# Micro.net
KiCad netlist of a schematic drawn in Altium Designer
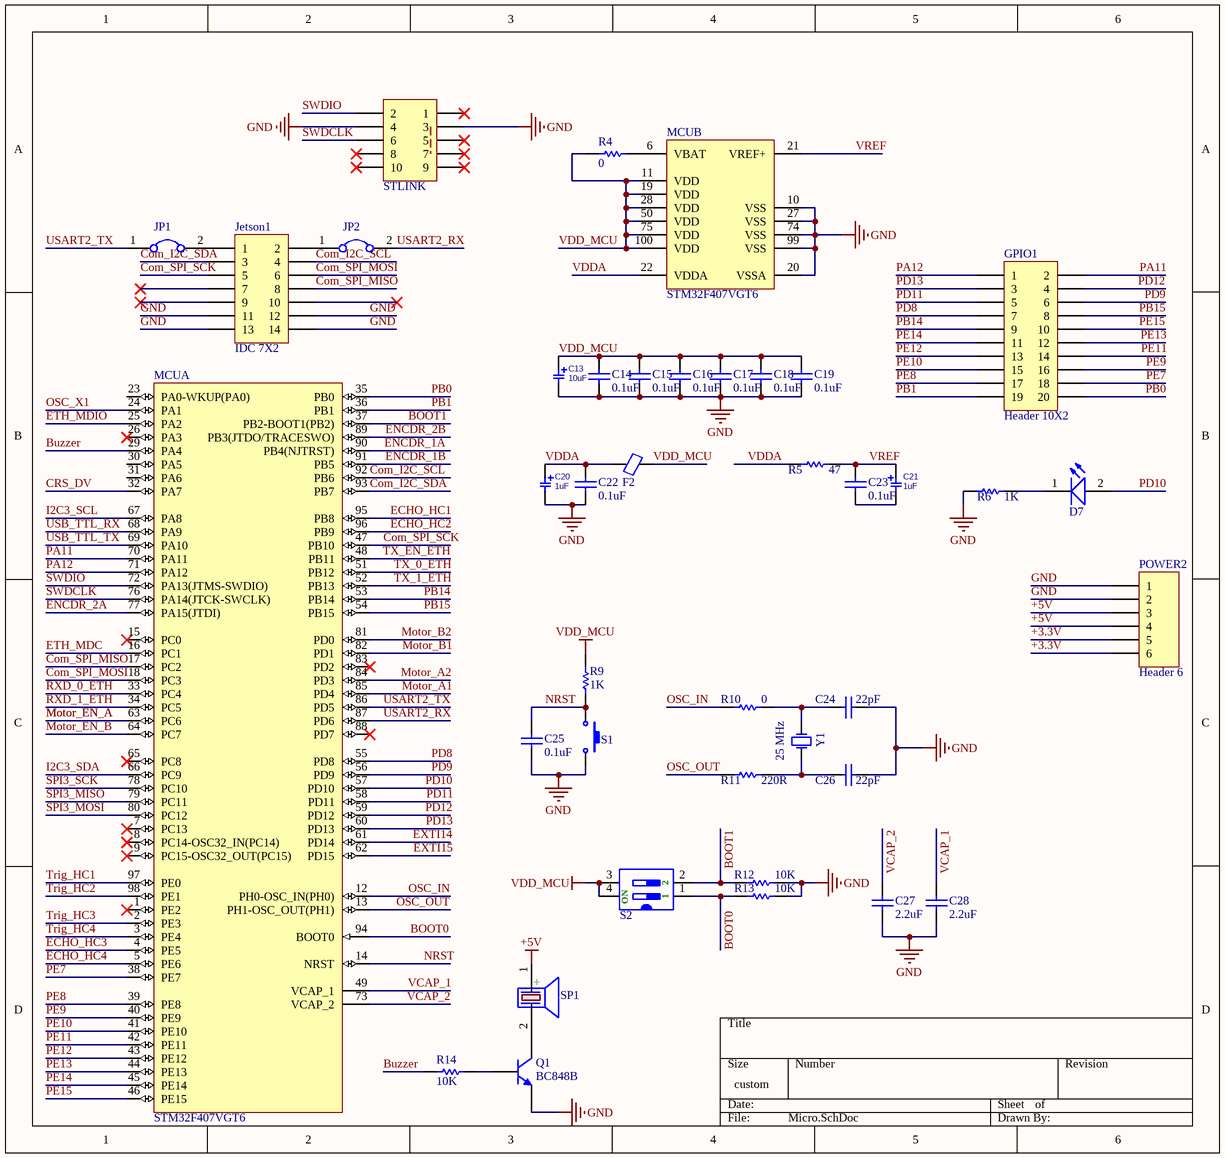
[diagram p0: Micro.SchDoc]

(export (version "E")
  (design (tool "Eeschema 10.0.6"))
  (components
    (comp (ref "C13")
      (value "10uF")
      (footprint "C_TN_6032")
      (description "CAP, SMD, TAN,")
      (libsource (lib "Passive") (part "CAP_SMD_TAN"))
    )
    (comp (ref "C14")
      (value "0.1uF")
      (footprint "CAPC3413X12N")
      (description "CAP 0805")
      (fields (field (name "DESIGNER") "Abbas Basereh"))
      (libsource (lib "Altium") (part "CAP SMD 0805"))
    )
    (comp (ref "C15")
      (value "0.1uF")
      (footprint "CAPC3413X12N")
      (description "CAP 0805")
      (fields (field (name "DESIGNER") "Abbas Basereh"))
      (libsource (lib "Altium") (part "CAP SMD 0805"))
    )
    (comp (ref "C16")
      (value "0.1uF")
      (footprint "CAPC3413X12N")
      (description "CAP 0805")
      (fields (field (name "DESIGNER") "Abbas Basereh"))
      (libsource (lib "Altium") (part "CAP SMD 0805"))
    )
    (comp (ref "C17")
      (value "0.1uF")
      (footprint "CAPC3413X12N")
      (description "CAP 0805")
      (fields (field (name "DESIGNER") "Abbas Basereh"))
      (libsource (lib "Altium") (part "CAP SMD 0805"))
    )
    (comp (ref "C18")
      (value "0.1uF")
      (footprint "CAPC3413X12N")
      (description "CAP 0805")
      (fields (field (name "DESIGNER") "Abbas Basereh"))
      (libsource (lib "Altium") (part "CAP SMD 0805"))
    )
    (comp (ref "C19")
      (value "0.1uF")
      (footprint "CAPC3413X12N")
      (description "CAP 0805")
      (fields (field (name "DESIGNER") "Abbas Basereh"))
      (libsource (lib "Altium") (part "CAP SMD 0805"))
    )
    (comp (ref "C20")
      (value "1uF")
      (footprint "C_TN_6032")
      (description "CAP, SMD, TAN,")
      (libsource (lib "Passive") (part "CAP_SMD_TAN"))
    )
    (comp (ref "C21")
      (value "1uF")
      (footprint "C_TN_6032")
      (description "CAP, SMD, TAN,")
      (libsource (lib "Passive") (part "CAP_SMD_TAN"))
    )
    (comp (ref "C22")
      (value "0.1uF")
      (footprint "CAPC3413X12N")
      (description "CAP 0805")
      (fields (field (name "DESIGNER") "Abbas Basereh"))
      (libsource (lib "Altium") (part "CAP SMD 0805"))
    )
    (comp (ref "C23")
      (value "0.1uF")
      (footprint "CAPC3413X12N")
      (description "CAP 0805")
      (fields (field (name "DESIGNER") "Abbas Basereh"))
      (libsource (lib "Altium") (part "CAP SMD 0805"))
    )
    (comp (ref "C24")
      (value "22pF")
      (footprint "CAPC3413X12N")
      (description "CAP 0805")
      (fields (field (name "DESIGNER") "Abbas Basereh"))
      (libsource (lib "Altium") (part "CAP SMD 0805"))
    )
    (comp (ref "C25")
      (value "0.1uF")
      (footprint "CAPC3413X12N")
      (description "CAP 0805")
      (fields (field (name "DESIGNER") "Abbas Basereh"))
      (libsource (lib "Altium") (part "CAP SMD 0805"))
    )
    (comp (ref "C26")
      (value "22pF")
      (footprint "CAPC3413X12N")
      (description "CAP 0805")
      (fields (field (name "DESIGNER") "Abbas Basereh"))
      (libsource (lib "Altium") (part "CAP SMD 0805"))
    )
    (comp (ref "C27")
      (value "2.2uF")
      (footprint "CAPC3413X12N")
      (description "CAP 0805")
      (fields (field (name "DESIGNER") "Abbas Basereh"))
      (libsource (lib "Altium") (part "CAP SMD 0805"))
    )
    (comp (ref "C28")
      (value "2.2uF")
      (footprint "CAPC3413X12N")
      (description "CAP 0805")
      (fields (field (name "DESIGNER") "Abbas Basereh"))
      (libsource (lib "Altium") (part "CAP SMD 0805"))
    )
    (comp (ref "D7")
      (value "LED SMD PACKAGE")
      (footprint "LED_SMD_0805")
      (description "SMD Mono-color Chip LED Waterclear")
      (fields (field (name "PART NUMBER") "150080BS75000") (field (name "PUBLISHER") "Ali Hafizi"))
      (libsource (lib "Altium") (part "LED SMD PACKAGE"))
    )
    (comp (ref "F2")
      (value "Ferrite Bead SMD")
      (footprint "FB0805")
      (fields (field (name "DESIGNER") "Ali Hafizi"))
      (libsource (lib "Altium") (part "Ferrite Bead SMD Package"))
    )
    (comp (ref "GPIO1")
      (value "Header 10X2")
      (footprint "HDR2X10")
      (description "Header, 10-Pin, Dual row")
      (fields (field (name "PUBLISHER") "Altium Limited"))
      (libsource (lib "Altium") (part "Header 10X2"))
    )
    (comp (ref "Jetson1")
      (value "IDC 7X2")
      (footprint "IDC 7X2:IDC 7X2")
      (libsource (lib "IDC 7X2") (part "IDC 7X2"))
    )
    (comp (ref "JP1")
      (value "Jumper")
      (footprint "Jumper Small - 2.54 - GRAY")
      (libsource (lib "Altium") (part "Jumper"))
    )
    (comp (ref "JP2")
      (value "Jumper")
      (footprint "Jumper Small - 2.54 - GRAY")
      (libsource (lib "Altium") (part "Jumper"))
    )
    (comp (ref "MCU")
      (value "STM32F407VGT6")
      (footprint "STM-LQFP100_N")
      (fields (field (name "MANUFACTURER") "STMicroelectronics"))
      (libsource (lib "STMicroelectronics STM32 F4") (part "STM32F407VGT6"))
    )
    (comp (ref "POWER2")
      (value "Header 6")
      (footprint "HDR1X6")
      (description "Header, 6-Pin")
      (fields (field (name "PUBLISHER") "Altium Limited"))
      (libsource (lib "Altium") (part "Header 6"))
    )
    (comp (ref "Q1")
      (value "BC848B")
      (footprint "SOT23_L")
      (description "NPN General-purpose Transistor")
      (fields (field (name "PUBLISHER") "Abbas Basereh"))
      (libsource (lib "Altium") (part "BC848B"))
    )
    (comp (ref "R4")
      (value "0")
      (footprint "RESC3413X04N")
      (description "RES 0805")
      (fields (field (name "DESIGNER") "Abbas Basereh"))
      (libsource (lib "Altium") (part "RES 0805 0.125W"))
    )
    (comp (ref "R5")
      (value "47")
      (footprint "RESC3413X04N")
      (description "RES 0805")
      (fields (field (name "DESIGNER") "Abbas Basereh"))
      (libsource (lib "Altium") (part "RES 0805 0.125W"))
    )
    (comp (ref "R6")
      (value "1K")
      (footprint "RESC3413X04N")
      (description "RES 0805")
      (fields (field (name "DESIGNER") "Abbas Basereh"))
      (libsource (lib "Altium") (part "RES 0805 0.125W"))
    )
    (comp (ref "R9")
      (value "1K")
      (footprint "RESC3413X04N")
      (description "RES 0805")
      (fields (field (name "DESIGNER") "Abbas Basereh"))
      (libsource (lib "Altium") (part "RES 0805 0.125W"))
    )
    (comp (ref "R10")
      (value "0")
      (footprint "RESC3413X04N")
      (description "RES 0805")
      (fields (field (name "DESIGNER") "Abbas Basereh"))
      (libsource (lib "Altium") (part "RES 0805 0.125W"))
    )
    (comp (ref "R11")
      (value "220R")
      (footprint "RESC3413X04N")
      (description "RES 0805")
      (fields (field (name "DESIGNER") "Abbas Basereh"))
      (libsource (lib "Altium") (part "RES 0805 0.125W"))
    )
    (comp (ref "R12")
      (value "10K")
      (footprint "RESC3413X04N")
      (description "RES 0805")
      (fields (field (name "DESIGNER") "Abbas Basereh"))
      (libsource (lib "Altium") (part "RES 0805 0.125W"))
    )
    (comp (ref "R13")
      (value "10K")
      (footprint "RESC3413X04N")
      (description "RES 0805")
      (fields (field (name "DESIGNER") "Abbas Basereh"))
      (libsource (lib "Altium") (part "RES 0805 0.125W"))
    )
    (comp (ref "R14")
      (value "10K")
      (footprint "RES0805_(2012X06L)")
      (description "TOTAL SMD RESISTOR PACK")
      (fields (field (name "DESIGNER") "Abbas Basereh"))
      (libsource (lib "Altium") (part "RES SMD PACKAGE"))
    )
    (comp (ref "S1")
      (value "Switch PB")
      (footprint "SW-PB")
      (description "Push Button Switch")
      (libsource (lib "Altium") (part "Switch PB"))
    )
    (comp (ref "S2")
      (value "SW_DIP_02")
      (footprint "SMV_DIP_CTS-219-02")
      (libsource (lib "SJ Switches") (part "SW_DIP_02"))
    )
    (comp (ref "SP1")
      (value "~")
      (footprint "BUZZER 7.62mm DC")
      (description "PIEZO BUZZER ACTIVE")
      (fields (field (name "DESIGNER") "Abbas Basereh") (field (name "PUBLISHER") "Abbas Basereh"))
      (libsource (lib "Altium") (part "PIEZO BUZZER"))
    )
    (comp (ref "STLINK")
      (value "CONNECTOR_IDC_5X2")
      (footprint "IDC2.54-10PIN")
      (description "IDC, 5-Pin, Dual row")
      (fields
        (field (name "MANUFACTURER") "CHINA")
        (field (name "PUBLISHER") "ABBAS BASEREH")
        (field (name "DESIGNER") "ABBAS BASEREH")
      )
      (libsource (lib "Altium") (part "IDC 5X2"))
    )
    (comp (ref "Y1")
      (value "25 MHz")
      (footprint "Crystal SMD")
      (description "XTAL Crystal")
      (fields (field (name "DESIGNER") "ABBAS BASEREH"))
      (libsource (lib "Altium") (part "XTAL"))
    )
  )
  (nets
    (net (code "1") (name "+5V") (class "Default")
      (node (ref "POWER2") (pin "3") (pinfunction "3_3") (pintype "passive"))
      (node (ref "POWER2") (pin "4") (pinfunction "4_4") (pintype "passive"))
      (node (ref "SP1") (pin "1") (pinfunction "+_1") (pintype "passive"))
    )
    (net (code "2") (name "/+3.3V") (class "Default")
      (node (ref "POWER2") (pin "5") (pinfunction "5_5") (pintype "passive"))
      (node (ref "POWER2") (pin "6") (pinfunction "6_6") (pintype "passive"))
    )
    (net (code "3") (name "/BOOT0") (class "Default")
      (node (ref "MCU") (pin "94") (pinfunction "BOOT0_94") (pintype "input"))
      (node (ref "R13") (pin "1") (pinfunction "1_1") (pintype "passive"))
      (node (ref "S2") (pin "1") (pinfunction "1_1") (pintype "passive"))
    )
    (net (code "4") (name "/BOOT1") (class "Default")
      (node (ref "MCU") (pin "37") (pinfunction "PB2-BOOT1(PB2)_37") (pintype "bidirectional"))
      (node (ref "R12") (pin "1") (pinfunction "1_1") (pintype "passive"))
      (node (ref "S2") (pin "2") (pinfunction "2_2") (pintype "passive"))
    )
    (net (code "5") (name "/Buzzer") (class "Default")
      (node (ref "MCU") (pin "29") (pinfunction "PA4_29") (pintype "bidirectional"))
      (node (ref "R14") (pin "1") (pinfunction "1_1") (pintype "passive"))
    )
    (net (code "6") (name "/CRS_DV") (class "Default")
      (node (ref "MCU") (pin "32") (pinfunction "PA7_32") (pintype "bidirectional"))
    )
    (net (code "7") (name "/Com_I2C_SCL") (class "Default")
      (node (ref "Jetson1") (pin "4") (pinfunction "4_4") (pintype "passive"))
      (node (ref "MCU") (pin "92") (pinfunction "PB6_92") (pintype "bidirectional"))
    )
    (net (code "8") (name "/Com_I2C_SDA") (class "Default")
      (node (ref "Jetson1") (pin "3") (pinfunction "3_3") (pintype "passive"))
      (node (ref "MCU") (pin "93") (pinfunction "PB7_93") (pintype "bidirectional"))
    )
    (net (code "9") (name "/Com_SPI_MISO") (class "Default")
      (node (ref "Jetson1") (pin "8") (pinfunction "8_8") (pintype "passive"))
      (node (ref "MCU") (pin "17") (pinfunction "PC2_17") (pintype "bidirectional"))
    )
    (net (code "10") (name "/Com_SPI_MOSI") (class "Default")
      (node (ref "Jetson1") (pin "6") (pinfunction "6_6") (pintype "passive"))
      (node (ref "MCU") (pin "18") (pinfunction "PC3_18") (pintype "bidirectional"))
    )
    (net (code "11") (name "/Com_SPI_SCK") (class "Default")
      (node (ref "Jetson1") (pin "5") (pinfunction "5_5") (pintype "passive"))
      (node (ref "MCU") (pin "47") (pinfunction "PB10_47") (pintype "bidirectional"))
    )
    (net (code "12") (name "/ECHO_HC1") (class "Default")
      (node (ref "MCU") (pin "95") (pinfunction "PB8_95") (pintype "bidirectional"))
    )
    (net (code "13") (name "/ECHO_HC2") (class "Default")
      (node (ref "MCU") (pin "96") (pinfunction "PB9_96") (pintype "bidirectional"))
    )
    (net (code "14") (name "/ECHO_HC3") (class "Default")
      (node (ref "MCU") (pin "4") (pinfunction "PE5_4") (pintype "bidirectional"))
    )
    (net (code "15") (name "/ECHO_HC4") (class "Default")
      (node (ref "MCU") (pin "5") (pinfunction "PE6_5") (pintype "bidirectional"))
    )
    (net (code "16") (name "/ENCDR_1A") (class "Default")
      (node (ref "MCU") (pin "90") (pinfunction "PB4(NJTRST)_90") (pintype "bidirectional"))
    )
    (net (code "17") (name "/ENCDR_1B") (class "Default")
      (node (ref "MCU") (pin "91") (pinfunction "PB5_91") (pintype "bidirectional"))
    )
    (net (code "18") (name "/ENCDR_2A") (class "Default")
      (node (ref "MCU") (pin "77") (pinfunction "PA15(JTDI)_77") (pintype "bidirectional"))
    )
    (net (code "19") (name "/ENCDR_2B") (class "Default")
      (node (ref "MCU") (pin "89") (pinfunction "PB3(JTDO/TRACESWO)_89") (pintype "bidirectional"))
    )
    (net (code "20") (name "/ETH_MDC") (class "Default")
      (node (ref "MCU") (pin "16") (pinfunction "PC1_16") (pintype "bidirectional"))
    )
    (net (code "21") (name "/ETH_MDIO") (class "Default")
      (node (ref "MCU") (pin "25") (pinfunction "PA2_25") (pintype "bidirectional"))
    )
    (net (code "22") (name "/EXTI14") (class "Default")
      (node (ref "MCU") (pin "61") (pinfunction "PD14_61") (pintype "bidirectional"))
    )
    (net (code "23") (name "/EXTI15") (class "Default")
      (node (ref "MCU") (pin "62") (pinfunction "PD15_62") (pintype "bidirectional"))
    )
    (net (code "24") (name "/I2C3_SCL") (class "Default")
      (node (ref "MCU") (pin "67") (pinfunction "PA8_67") (pintype "bidirectional"))
    )
    (net (code "25") (name "/I2C3_SDA") (class "Default")
      (node (ref "MCU") (pin "66") (pinfunction "PC9_66") (pintype "bidirectional"))
    )
    (net (code "26") (name "/Motor_A1") (class "Default")
      (node (ref "MCU") (pin "85") (pinfunction "PD4_85") (pintype "bidirectional"))
    )
    (net (code "27") (name "/Motor_A2") (class "Default")
      (node (ref "MCU") (pin "84") (pinfunction "PD3_84") (pintype "bidirectional"))
    )
    (net (code "28") (name "/Motor_B1") (class "Default")
      (node (ref "MCU") (pin "82") (pinfunction "PD1_82") (pintype "bidirectional"))
    )
    (net (code "29") (name "/Motor_B2") (class "Default")
      (node (ref "MCU") (pin "81") (pinfunction "PD0_81") (pintype "bidirectional"))
    )
    (net (code "30") (name "/Motor_EN_A") (class "Default")
      (node (ref "MCU") (pin "63") (pinfunction "PC6_63") (pintype "bidirectional"))
    )
    (net (code "31") (name "/Motor_EN_B") (class "Default")
      (node (ref "MCU") (pin "64") (pinfunction "PC7_64") (pintype "bidirectional"))
    )
    (net (code "32") (name "/NRST") (class "Default")
      (node (ref "C25") (pin "2") (pinfunction "2_2") (pintype "passive"))
      (node (ref "MCU") (pin "14") (pinfunction "NRST_14") (pintype "bidirectional"))
      (node (ref "R9") (pin "1") (pinfunction "1_1") (pintype "passive"))
      (node (ref "S1") (pin "1") (pinfunction "1_1") (pintype "passive"))
    )
    (net (code "33") (name "/OSC_IN") (class "Default")
      (node (ref "MCU") (pin "12") (pinfunction "PH0-OSC_IN(PH0)_12") (pintype "bidirectional"))
      (node (ref "R10") (pin "1") (pinfunction "1_1") (pintype "passive"))
    )
    (net (code "34") (name "/OSC_OUT") (class "Default")
      (node (ref "MCU") (pin "13") (pinfunction "PH1-OSC_OUT(PH1)_13") (pintype "bidirectional"))
      (node (ref "R11") (pin "1") (pinfunction "1_1") (pintype "passive"))
    )
    (net (code "35") (name "/OSC_X1") (class "Default")
      (node (ref "MCU") (pin "24") (pinfunction "PA1_24") (pintype "bidirectional"))
    )
    (net (code "36") (name "/PA11") (class "Default")
      (node (ref "GPIO1") (pin "2") (pinfunction "2_2") (pintype "passive"))
      (node (ref "MCU") (pin "70") (pinfunction "PA11_70") (pintype "bidirectional"))
    )
    (net (code "37") (name "/PA12") (class "Default")
      (node (ref "GPIO1") (pin "1") (pinfunction "1_1") (pintype "passive"))
      (node (ref "MCU") (pin "71") (pinfunction "PA12_71") (pintype "bidirectional"))
    )
    (net (code "38") (name "/PB0") (class "Default")
      (node (ref "GPIO1") (pin "20") (pinfunction "20_20") (pintype "passive"))
      (node (ref "MCU") (pin "35") (pinfunction "PB0_35") (pintype "bidirectional"))
    )
    (net (code "39") (name "/PB1") (class "Default")
      (node (ref "GPIO1") (pin "19") (pinfunction "19_19") (pintype "passive"))
      (node (ref "MCU") (pin "36") (pinfunction "PB1_36") (pintype "bidirectional"))
    )
    (net (code "40") (name "/PB14") (class "Default")
      (node (ref "GPIO1") (pin "9") (pinfunction "9_9") (pintype "passive"))
      (node (ref "MCU") (pin "53") (pinfunction "PB14_53") (pintype "bidirectional"))
    )
    (net (code "41") (name "/PB15") (class "Default")
      (node (ref "GPIO1") (pin "8") (pinfunction "8_8") (pintype "passive"))
      (node (ref "MCU") (pin "54") (pinfunction "PB15_54") (pintype "bidirectional"))
    )
    (net (code "42") (name "/PD8") (class "Default")
      (node (ref "GPIO1") (pin "7") (pinfunction "7_7") (pintype "passive"))
      (node (ref "MCU") (pin "55") (pinfunction "PD8_55") (pintype "bidirectional"))
    )
    (net (code "43") (name "/PD9") (class "Default")
      (node (ref "GPIO1") (pin "6") (pinfunction "6_6") (pintype "passive"))
      (node (ref "MCU") (pin "56") (pinfunction "PD9_56") (pintype "bidirectional"))
    )
    (net (code "44") (name "/PD10") (class "Default")
      (node (ref "D7") (pin "2") (pinfunction "A_2") (pintype "passive"))
      (node (ref "MCU") (pin "57") (pinfunction "PD10_57") (pintype "bidirectional"))
    )
    (net (code "45") (name "/PD11") (class "Default")
      (node (ref "GPIO1") (pin "5") (pinfunction "5_5") (pintype "passive"))
      (node (ref "MCU") (pin "58") (pinfunction "PD11_58") (pintype "bidirectional"))
    )
    (net (code "46") (name "/PD12") (class "Default")
      (node (ref "GPIO1") (pin "4") (pinfunction "4_4") (pintype "passive"))
      (node (ref "MCU") (pin "59") (pinfunction "PD12_59") (pintype "bidirectional"))
    )
    (net (code "47") (name "/PD13") (class "Default")
      (node (ref "GPIO1") (pin "3") (pinfunction "3_3") (pintype "passive"))
      (node (ref "MCU") (pin "60") (pinfunction "PD13_60") (pintype "bidirectional"))
    )
    (net (code "48") (name "/PE7") (class "Default")
      (node (ref "GPIO1") (pin "18") (pinfunction "18_18") (pintype "passive"))
      (node (ref "MCU") (pin "38") (pinfunction "PE7_38") (pintype "bidirectional"))
    )
    (net (code "49") (name "/PE8") (class "Default")
      (node (ref "GPIO1") (pin "17") (pinfunction "17_17") (pintype "passive"))
      (node (ref "MCU") (pin "39") (pinfunction "PE8_39") (pintype "bidirectional"))
    )
    (net (code "50") (name "/PE9") (class "Default")
      (node (ref "GPIO1") (pin "16") (pinfunction "16_16") (pintype "passive"))
      (node (ref "MCU") (pin "40") (pinfunction "PE9_40") (pintype "bidirectional"))
    )
    (net (code "51") (name "/PE10") (class "Default")
      (node (ref "GPIO1") (pin "15") (pinfunction "15_15") (pintype "passive"))
      (node (ref "MCU") (pin "41") (pinfunction "PE10_41") (pintype "bidirectional"))
    )
    (net (code "52") (name "/PE11") (class "Default")
      (node (ref "GPIO1") (pin "14") (pinfunction "14_14") (pintype "passive"))
      (node (ref "MCU") (pin "42") (pinfunction "PE11_42") (pintype "bidirectional"))
    )
    (net (code "53") (name "/PE12") (class "Default")
      (node (ref "GPIO1") (pin "13") (pinfunction "13_13") (pintype "passive"))
      (node (ref "MCU") (pin "43") (pinfunction "PE12_43") (pintype "bidirectional"))
    )
    (net (code "54") (name "/PE13") (class "Default")
      (node (ref "GPIO1") (pin "12") (pinfunction "12_12") (pintype "passive"))
      (node (ref "MCU") (pin "44") (pinfunction "PE13_44") (pintype "bidirectional"))
    )
    (net (code "55") (name "/PE14") (class "Default")
      (node (ref "GPIO1") (pin "11") (pinfunction "11_11") (pintype "passive"))
      (node (ref "MCU") (pin "45") (pinfunction "PE14_45") (pintype "bidirectional"))
    )
    (net (code "56") (name "/PE15") (class "Default")
      (node (ref "GPIO1") (pin "10") (pinfunction "10_10") (pintype "passive"))
      (node (ref "MCU") (pin "46") (pinfunction "PE15_46") (pintype "bidirectional"))
    )
    (net (code "57") (name "/RXD_0_ETH") (class "Default")
      (node (ref "MCU") (pin "33") (pinfunction "PC4_33") (pintype "bidirectional"))
    )
    (net (code "58") (name "/RXD_1_ETH") (class "Default")
      (node (ref "MCU") (pin "34") (pinfunction "PC5_34") (pintype "bidirectional"))
    )
    (net (code "59") (name "/SPI3_MISO") (class "Default")
      (node (ref "MCU") (pin "79") (pinfunction "PC11_79") (pintype "bidirectional"))
    )
    (net (code "60") (name "/SPI3_MOSI") (class "Default")
      (node (ref "MCU") (pin "80") (pinfunction "PC12_80") (pintype "bidirectional"))
    )
    (net (code "61") (name "/SPI3_SCK") (class "Default")
      (node (ref "MCU") (pin "78") (pinfunction "PC10_78") (pintype "bidirectional"))
    )
    (net (code "62") (name "/SWDCLK") (class "Default")
      (node (ref "MCU") (pin "76") (pinfunction "PA14(JTCK-SWCLK)_76") (pintype "bidirectional"))
      (node (ref "STLINK") (pin "6") (pinfunction "6_6") (pintype "passive"))
    )
    (net (code "63") (name "/SWDIO") (class "Default")
      (node (ref "MCU") (pin "72") (pinfunction "PA13(JTMS-SWDIO)_72") (pintype "bidirectional"))
      (node (ref "STLINK") (pin "2") (pinfunction "2_2") (pintype "passive"))
    )
    (net (code "64") (name "/TX_0_ETH") (class "Default")
      (node (ref "MCU") (pin "51") (pinfunction "PB12_51") (pintype "bidirectional"))
    )
    (net (code "65") (name "/TX_1_ETH") (class "Default")
      (node (ref "MCU") (pin "52") (pinfunction "PB13_52") (pintype "bidirectional"))
    )
    (net (code "66") (name "/TX_EN_ETH") (class "Default")
      (node (ref "MCU") (pin "48") (pinfunction "PB11_48") (pintype "bidirectional"))
    )
    (net (code "67") (name "/Trig_HC1") (class "Default")
      (node (ref "MCU") (pin "97") (pinfunction "PE0_97") (pintype "bidirectional"))
    )
    (net (code "68") (name "/Trig_HC2") (class "Default")
      (node (ref "MCU") (pin "98") (pinfunction "PE1_98") (pintype "bidirectional"))
    )
    (net (code "69") (name "/Trig_HC3") (class "Default")
      (node (ref "MCU") (pin "2") (pinfunction "PE3_2") (pintype "bidirectional"))
    )
    (net (code "70") (name "/Trig_HC4") (class "Default")
      (node (ref "MCU") (pin "3") (pinfunction "PE4_3") (pintype "bidirectional"))
    )
    (net (code "71") (name "/USART2_RX") (class "Default")
      (node (ref "JP2") (pin "2") (pinfunction "2_2") (pintype "passive"))
      (node (ref "MCU") (pin "87") (pinfunction "PD6_87") (pintype "bidirectional"))
    )
    (net (code "72") (name "/USART2_TX") (class "Default")
      (node (ref "JP1") (pin "1") (pinfunction "1_1") (pintype "passive"))
      (node (ref "MCU") (pin "86") (pinfunction "PD5_86") (pintype "bidirectional"))
    )
    (net (code "73") (name "/USB_TTL_RX") (class "Default")
      (node (ref "MCU") (pin "68") (pinfunction "PA9_68") (pintype "bidirectional"))
    )
    (net (code "74") (name "/USB_TTL_TX") (class "Default")
      (node (ref "MCU") (pin "69") (pinfunction "PA10_69") (pintype "bidirectional"))
    )
    (net (code "75") (name "/VCAP_1") (class "Default")
      (node (ref "C28") (pin "2") (pinfunction "2_2") (pintype "passive"))
      (node (ref "MCU") (pin "49") (pinfunction "VCAP_1_49") (pintype "power_in"))
    )
    (net (code "76") (name "/VCAP_2") (class "Default")
      (node (ref "C27") (pin "2") (pinfunction "2_2") (pintype "passive"))
      (node (ref "MCU") (pin "73") (pinfunction "VCAP_2_73") (pintype "power_in"))
    )
    (net (code "77") (name "/VDDA") (class "Default")
      (node (ref "C20") (pin "1") (pinfunction "1_1") (pintype "passive"))
      (node (ref "C22") (pin "2") (pinfunction "2_2") (pintype "passive"))
      (node (ref "F2") (pin "1") (pinfunction "1_1") (pintype "passive"))
      (node (ref "MCU") (pin "22") (pinfunction "VDDA_22") (pintype "power_in"))
      (node (ref "R5") (pin "1") (pinfunction "1_1") (pintype "passive"))
    )
    (net (code "78") (name "/VREF") (class "Default")
      (node (ref "C21") (pin "1") (pinfunction "1_1") (pintype "passive"))
      (node (ref "C23") (pin "2") (pinfunction "2_2") (pintype "passive"))
      (node (ref "MCU") (pin "21") (pinfunction "VREF+_21") (pintype "power_in"))
      (node (ref "R5") (pin "2") (pinfunction "2_2") (pintype "passive"))
    )
    (net (code "79") (name "GND") (class "Default")
      (node (ref "C13") (pin "2") (pinfunction "2_2") (pintype "passive"))
      (node (ref "C14") (pin "1") (pinfunction "1_1") (pintype "passive"))
      (node (ref "C15") (pin "1") (pinfunction "1_1") (pintype "passive"))
      (node (ref "C16") (pin "1") (pinfunction "1_1") (pintype "passive"))
      (node (ref "C17") (pin "1") (pinfunction "1_1") (pintype "passive"))
      (node (ref "C18") (pin "1") (pinfunction "1_1") (pintype "passive"))
      (node (ref "C19") (pin "1") (pinfunction "1_1") (pintype "passive"))
      (node (ref "C20") (pin "2") (pinfunction "2_2") (pintype "passive"))
      (node (ref "C22") (pin "1") (pinfunction "1_1") (pintype "passive"))
      (node (ref "C24") (pin "1") (pinfunction "1_1") (pintype "passive"))
      (node (ref "C25") (pin "1") (pinfunction "1_1") (pintype "passive"))
      (node (ref "C26") (pin "1") (pinfunction "1_1") (pintype "passive"))
      (node (ref "C27") (pin "1") (pinfunction "1_1") (pintype "passive"))
      (node (ref "C28") (pin "1") (pinfunction "1_1") (pintype "passive"))
      (node (ref "Jetson1") (pin "11") (pinfunction "11_11") (pintype "passive"))
      (node (ref "Jetson1") (pin "12") (pinfunction "12_12") (pintype "passive"))
      (node (ref "Jetson1") (pin "13") (pinfunction "13_13") (pintype "passive"))
      (node (ref "Jetson1") (pin "14") (pinfunction "14_14") (pintype "passive"))
      (node (ref "MCU") (pin "10") (pinfunction "VSS_10") (pintype "power_in"))
      (node (ref "MCU") (pin "20") (pinfunction "VSSA_20") (pintype "power_in"))
      (node (ref "MCU") (pin "27") (pinfunction "VSS_27") (pintype "power_in"))
      (node (ref "MCU") (pin "74") (pinfunction "VSS_74") (pintype "power_in"))
      (node (ref "MCU") (pin "99") (pinfunction "VSS_99") (pintype "power_in"))
      (node (ref "POWER2") (pin "1") (pinfunction "1_1") (pintype "passive"))
      (node (ref "POWER2") (pin "2") (pinfunction "2_2") (pintype "passive"))
      (node (ref "Q1") (pin "2") (pinfunction "E_2") (pintype "passive"))
      (node (ref "R12") (pin "2") (pinfunction "2_2") (pintype "passive"))
      (node (ref "R13") (pin "2") (pinfunction "2_2") (pintype "passive"))
      (node (ref "R6") (pin "1") (pinfunction "1_1") (pintype "passive"))
      (node (ref "S1") (pin "2") (pinfunction "2_2") (pintype "passive"))
      (node (ref "STLINK") (pin "3") (pinfunction "3_3") (pintype "passive"))
      (node (ref "STLINK") (pin "4") (pinfunction "4_4") (pintype "passive"))
    )
    (net (code "80") (name "Net-(C21-Pad2)") (class "Default")
      (node (ref "C21") (pin "2") (pinfunction "2_2") (pintype "passive"))
      (node (ref "C23") (pin "1") (pinfunction "1_1") (pintype "passive"))
    )
    (net (code "81") (name "Net-(D7-K)") (class "Default")
      (node (ref "D7") (pin "1") (pinfunction "K_1") (pintype "passive"))
      (node (ref "R6") (pin "2") (pinfunction "2_2") (pintype "passive"))
    )
    (net (code "82") (name "Net-(JP1-Pad2)") (class "Default")
      (node (ref "JP1") (pin "2") (pinfunction "2_2") (pintype "passive"))
      (node (ref "Jetson1") (pin "1") (pinfunction "1_1") (pintype "passive"))
    )
    (net (code "83") (name "Net-(JP2-Pad1)") (class "Default")
      (node (ref "JP2") (pin "1") (pinfunction "1_1") (pintype "passive"))
      (node (ref "Jetson1") (pin "2") (pinfunction "2_2") (pintype "passive"))
    )
    (net (code "84") (name "Net-(MCUB-VBAT)") (class "Default")
      (node (ref "MCU") (pin "6") (pinfunction "VBAT_6") (pintype "power_in"))
      (node (ref "R4") (pin "2") (pinfunction "2_2") (pintype "passive"))
    )
    (net (code "85") (name "Net-(Q1-B)") (class "Default")
      (node (ref "Q1") (pin "1") (pinfunction "B_1") (pintype "passive"))
      (node (ref "R14") (pin "2") (pinfunction "2_2") (pintype "passive"))
    )
    (net (code "86") (name "Net-(Q1-C)") (class "Default")
      (node (ref "Q1") (pin "3") (pinfunction "C_3") (pintype "passive"))
      (node (ref "SP1") (pin "2") (pinfunction "-_2") (pintype "passive"))
    )
    (net (code "87") (name "Net-(Y1-OSC1)") (class "Default")
      (node (ref "C26") (pin "2") (pinfunction "2_2") (pintype "passive"))
      (node (ref "R11") (pin "2") (pinfunction "2_2") (pintype "passive"))
      (node (ref "Y1") (pin "1") (pinfunction "OSC1_1") (pintype "passive"))
    )
    (net (code "88") (name "Net-(Y1-OSC2)") (class "Default")
      (node (ref "C24") (pin "2") (pinfunction "2_2") (pintype "passive"))
      (node (ref "R10") (pin "2") (pinfunction "2_2") (pintype "passive"))
      (node (ref "Y1") (pin "2") (pinfunction "OSC2_2") (pintype "passive"))
    )
    (net (code "89") (name "VDD_MCU") (class "Default")
      (node (ref "C13") (pin "1") (pinfunction "1_1") (pintype "passive"))
      (node (ref "C14") (pin "2") (pinfunction "2_2") (pintype "passive"))
      (node (ref "C15") (pin "2") (pinfunction "2_2") (pintype "passive"))
      (node (ref "C16") (pin "2") (pinfunction "2_2") (pintype "passive"))
      (node (ref "C17") (pin "2") (pinfunction "2_2") (pintype "passive"))
      (node (ref "C18") (pin "2") (pinfunction "2_2") (pintype "passive"))
      (node (ref "C19") (pin "2") (pinfunction "2_2") (pintype "passive"))
      (node (ref "F2") (pin "2") (pinfunction "2_2") (pintype "passive"))
      (node (ref "MCU") (pin "100") (pinfunction "VDD_100") (pintype "power_in"))
      (node (ref "MCU") (pin "11") (pinfunction "VDD_11") (pintype "power_in"))
      (node (ref "MCU") (pin "19") (pinfunction "VDD_19") (pintype "power_in"))
      (node (ref "MCU") (pin "28") (pinfunction "VDD_28") (pintype "power_in"))
      (node (ref "MCU") (pin "50") (pinfunction "VDD_50") (pintype "power_in"))
      (node (ref "MCU") (pin "75") (pinfunction "VDD_75") (pintype "power_in"))
      (node (ref "R4") (pin "1") (pinfunction "1_1") (pintype "passive"))
      (node (ref "R9") (pin "2") (pinfunction "2_2") (pintype "passive"))
      (node (ref "S2") (pin "3") (pinfunction "3_3") (pintype "passive"))
      (node (ref "S2") (pin "4") (pinfunction "4_4") (pintype "passive"))
    )
    (net (code "90") (name "unconnected-(Jetson1-Pad7)") (class "Default")
      (node (ref "Jetson1") (pin "7") (pinfunction "7_7") (pintype "passive+no_connect"))
    )
    (net (code "91") (name "unconnected-(Jetson1-Pad9)") (class "Default")
      (node (ref "Jetson1") (pin "9") (pinfunction "9_9") (pintype "passive+no_connect"))
    )
    (net (code "92") (name "unconnected-(Jetson1-Pad10)") (class "Default")
      (node (ref "Jetson1") (pin "10") (pinfunction "10_10") (pintype "passive+no_connect"))
    )
    (net (code "93") (name "unconnected-(MCUA-PA0-WKUP(PA0)-Pad23)") (class "Default")
      (node (ref "MCU") (pin "23") (pinfunction "PA0-WKUP(PA0)_23") (pintype "bidirectional"))
    )
    (net (code "94") (name "unconnected-(MCUA-PA3-Pad26)") (class "Default")
      (node (ref "MCU") (pin "26") (pinfunction "PA3_26") (pintype "bidirectional+no_connect"))
    )
    (net (code "95") (name "unconnected-(MCUA-PA5-Pad30)") (class "Default")
      (node (ref "MCU") (pin "30") (pinfunction "PA5_30") (pintype "bidirectional"))
    )
    (net (code "96") (name "unconnected-(MCUA-PA6-Pad31)") (class "Default")
      (node (ref "MCU") (pin "31") (pinfunction "PA6_31") (pintype "bidirectional"))
    )
    (net (code "97") (name "unconnected-(MCUA-PC0-Pad15)") (class "Default")
      (node (ref "MCU") (pin "15") (pinfunction "PC0_15") (pintype "bidirectional+no_connect"))
    )
    (net (code "98") (name "unconnected-(MCUA-PC8-Pad65)") (class "Default")
      (node (ref "MCU") (pin "65") (pinfunction "PC8_65") (pintype "bidirectional+no_connect"))
    )
    (net (code "99") (name "unconnected-(MCUA-PC13-Pad7)") (class "Default")
      (node (ref "MCU") (pin "7") (pinfunction "PC13_7") (pintype "bidirectional+no_connect"))
    )
    (net (code "100") (name "unconnected-(MCUA-PC14-OSC32_IN(PC14)-Pad8)") (class "Default")
      (node (ref "MCU") (pin "8") (pinfunction "PC14-OSC32_IN(PC14)_8") (pintype "bidirectional+no_connect"))
    )
    (net (code "101") (name "unconnected-(MCUA-PC15-OSC32_OUT(PC15)-Pad9)") (class "Default")
      (node (ref "MCU") (pin "9") (pinfunction "PC15-OSC32_OUT(PC15)_9") (pintype "bidirectional+no_connect"))
    )
    (net (code "102") (name "unconnected-(MCUA-PD2-Pad83)") (class "Default")
      (node (ref "MCU") (pin "83") (pinfunction "PD2_83") (pintype "bidirectional+no_connect"))
    )
    (net (code "103") (name "unconnected-(MCUA-PD7-Pad88)") (class "Default")
      (node (ref "MCU") (pin "88") (pinfunction "PD7_88") (pintype "bidirectional+no_connect"))
    )
    (net (code "104") (name "unconnected-(MCUA-PE2-Pad1)") (class "Default")
      (node (ref "MCU") (pin "1") (pinfunction "PE2_1") (pintype "bidirectional+no_connect"))
    )
    (net (code "105") (name "unconnected-(STLINK-Pad1)") (class "Default")
      (node (ref "STLINK") (pin "1") (pinfunction "1_1") (pintype "passive+no_connect"))
    )
    (net (code "106") (name "unconnected-(STLINK-Pad5)") (class "Default")
      (node (ref "STLINK") (pin "5") (pinfunction "5_5") (pintype "passive+no_connect"))
    )
    (net (code "107") (name "unconnected-(STLINK-Pad7)") (class "Default")
      (node (ref "STLINK") (pin "7") (pinfunction "7_7") (pintype "passive+no_connect"))
    )
    (net (code "108") (name "unconnected-(STLINK-Pad8)") (class "Default")
      (node (ref "STLINK") (pin "8") (pinfunction "8_8") (pintype "passive+no_connect"))
    )
    (net (code "109") (name "unconnected-(STLINK-Pad9)") (class "Default")
      (node (ref "STLINK") (pin "9") (pinfunction "9_9") (pintype "passive+no_connect"))
    )
    (net (code "110") (name "unconnected-(STLINK-Pad10)") (class "Default")
      (node (ref "STLINK") (pin "10") (pinfunction "10_10") (pintype "passive+no_connect"))
    )
  )
)
